# 00003_2020-06-15_05-30-21.net
KiCad netlist of a schematic drawn in EasyEDA
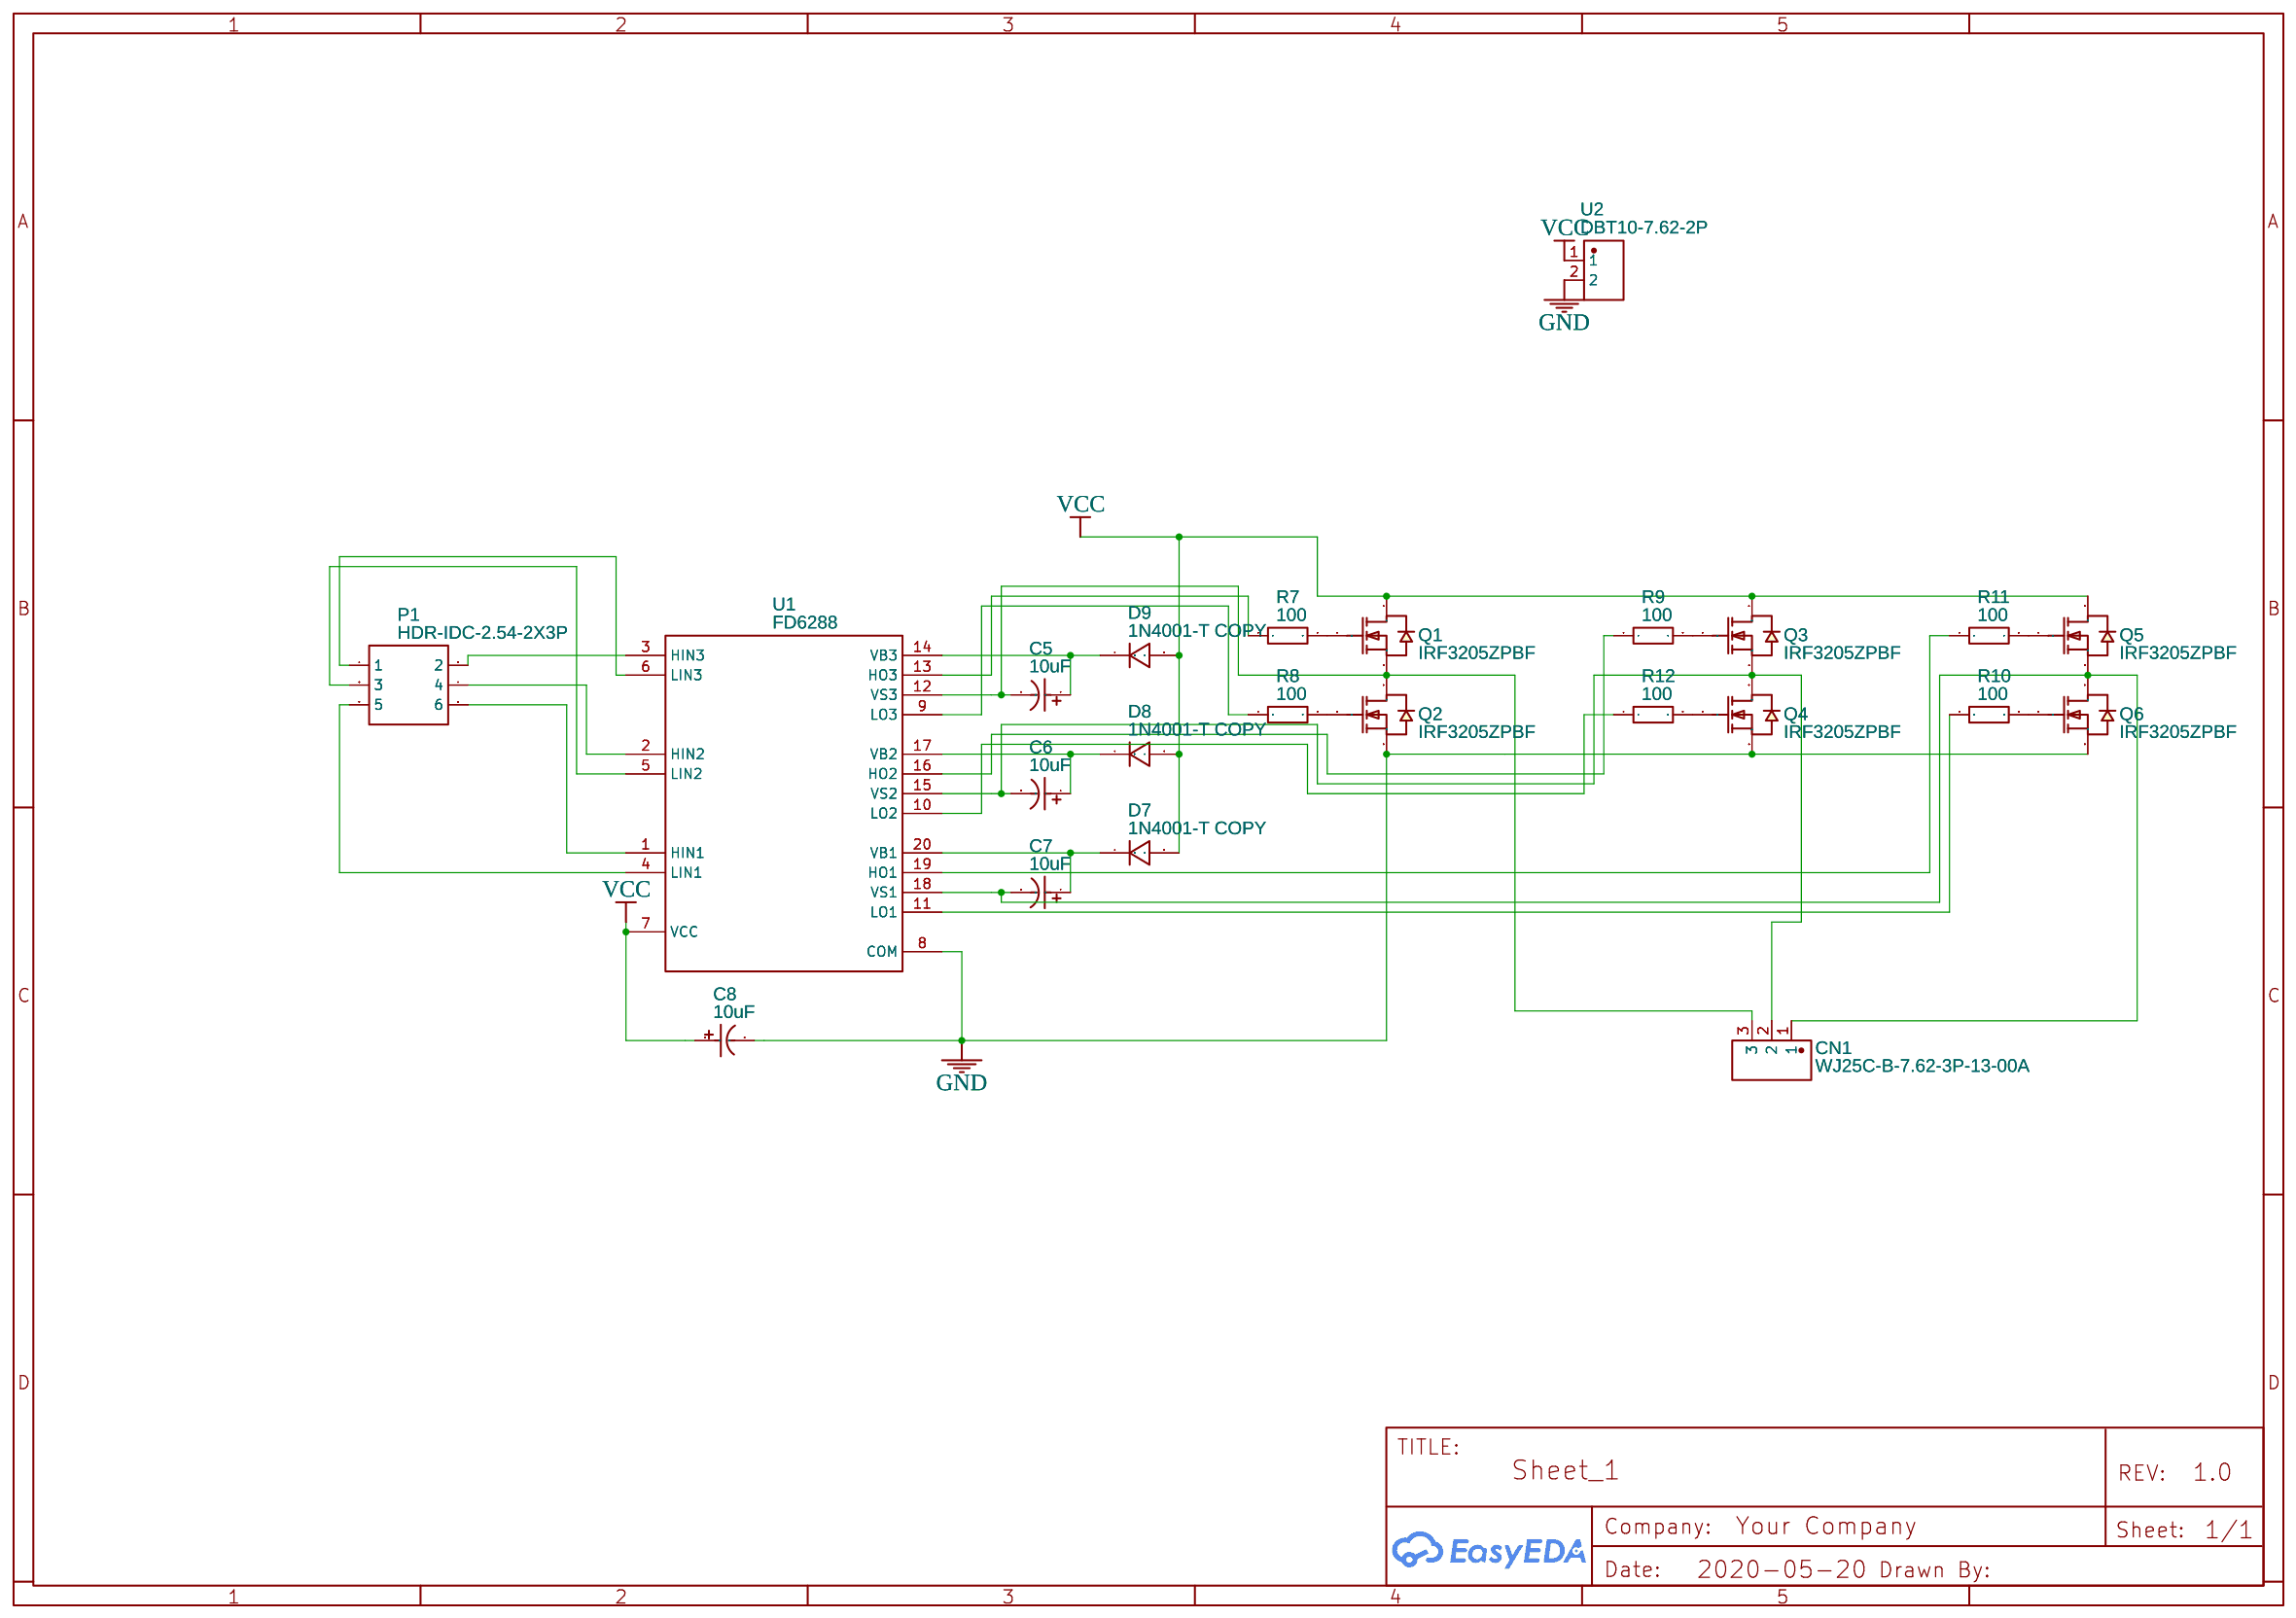
[diagram p0: schematic sheet]

(export (version "E")
  (design (tool "Eeschema 10.0.6"))
  (components
    (comp (ref "C5")
      (value "10uF")
      (fields
        (field (name "BOM_Manufacturer Part") "10uF 25V 5*11")
        (field (name "BOM_Supplier Part") "C43347")
      )
      (libsource (lib "") (part "10uF 25V 5*11"))
    )
    (comp (ref "C6")
      (value "10uF")
      (fields
        (field (name "BOM_Manufacturer Part") "10uF 25V 5*11")
        (field (name "BOM_Supplier Part") "C43347")
      )
      (libsource (lib "") (part "10uF 25V 5*11"))
    )
    (comp (ref "C7")
      (value "10uF")
      (fields
        (field (name "BOM_Manufacturer Part") "10uF 25V 5*11")
        (field (name "BOM_Supplier Part") "C43347")
      )
      (libsource (lib "") (part "10uF 25V 5*11"))
    )
    (comp (ref "C8")
      (value "10uF")
      (fields
        (field (name "BOM_Manufacturer Part") "10uF 25V 5*11")
        (field (name "BOM_Supplier Part") "C43347")
      )
      (libsource (lib "") (part "10uF 25V 5*11_1"))
    )
    (comp (ref "CN1")
      (value "WJ25C-B-7.62-3P-13-00A")
      (fields (field (name "BOM_Supplier Part") "C61583"))
      (libsource (lib "") (part "WJ25C-B-7.62-3P-13-00A"))
    )
    (comp (ref "D7")
      (value "1N4001-T COPY")
      (fields (field (name "BOM_Manufacturer Part") "1N4001-T") (field (name "BOM_Supplier Part") "C99656"))
      (libsource (lib "") (part "1N4001-T COPY"))
    )
    (comp (ref "D8")
      (value "1N4001-T COPY")
      (fields (field (name "BOM_Manufacturer Part") "1N4001-T") (field (name "BOM_Supplier Part") "C99656"))
      (libsource (lib "") (part "1N4001-T COPY"))
    )
    (comp (ref "D9")
      (value "1N4001-T COPY")
      (fields (field (name "BOM_Manufacturer Part") "1N4001-T") (field (name "BOM_Supplier Part") "C99656"))
      (libsource (lib "") (part "1N4001-T COPY"))
    )
    (comp (ref "P1")
      (value "HDR-IDC-2.54-2X3P")
      (fields
        (field (name "BOM_Manufacturer Part") "2X3 2.54mm IDC Box")
        (field (name "BOM_Supplier Part") "C11214")
      )
      (libsource (lib "") (part "HDR-IDC-2.54-2X3P"))
    )
    (comp (ref "Q1")
      (value "IRF3205ZPBF")
      (fields (field (name "BOM_Supplier Part") "C2612"))
      (libsource (lib "") (part "IRF3205ZPBF"))
    )
    (comp (ref "Q2")
      (value "IRF3205ZPBF")
      (fields (field (name "BOM_Supplier Part") "C2612"))
      (libsource (lib "") (part "IRF3205ZPBF"))
    )
    (comp (ref "Q3")
      (value "IRF3205ZPBF")
      (fields (field (name "BOM_Supplier Part") "C2612"))
      (libsource (lib "") (part "IRF3205ZPBF"))
    )
    (comp (ref "Q4")
      (value "IRF3205ZPBF")
      (fields (field (name "BOM_Supplier Part") "C2612"))
      (libsource (lib "") (part "IRF3205ZPBF"))
    )
    (comp (ref "Q5")
      (value "IRF3205ZPBF")
      (fields (field (name "BOM_Supplier Part") "C2612"))
      (libsource (lib "") (part "IRF3205ZPBF"))
    )
    (comp (ref "Q6")
      (value "IRF3205ZPBF")
      (fields (field (name "BOM_Supplier Part") "C2612"))
      (libsource (lib "") (part "IRF3205ZPBF"))
    )
    (comp (ref "R7")
      (value "100")
      (fields (field (name "BOM_Supplier Part") "C120031"))
      (libsource (lib "") (part "CF1/4W-100Ω±5% T52"))
    )
    (comp (ref "R8")
      (value "100")
      (fields (field (name "BOM_Supplier Part") "C120031"))
      (libsource (lib "") (part "CF1/4W-100Ω±5% T52"))
    )
    (comp (ref "R9")
      (value "100")
      (fields (field (name "BOM_Supplier Part") "C120031"))
      (libsource (lib "") (part "CF1/4W-100Ω±5% T52"))
    )
    (comp (ref "R10")
      (value "100")
      (fields (field (name "BOM_Supplier Part") "C120031"))
      (libsource (lib "") (part "CF1/4W-100Ω±5% T52"))
    )
    (comp (ref "R11")
      (value "100")
      (fields (field (name "BOM_Supplier Part") "C120031"))
      (libsource (lib "") (part "CF1/4W-100Ω±5% T52"))
    )
    (comp (ref "R12")
      (value "100")
      (fields (field (name "BOM_Supplier Part") "C120031"))
      (libsource (lib "") (part "CF1/4W-100Ω±5% T52"))
    )
    (comp (ref "U1")
      (value "FD6288")
      (fields (field (name "BOM_Supplier Part") "C97683"))
      (libsource (lib "") (part "FD6288"))
    )
    (comp (ref "U2")
      (value "DBT10-7.62-2P")
      (fields (field (name "BOM_Supplier Part") "C395930"))
      (libsource (lib "") (part "DBT10-7.62-2P"))
    )
  )
  (nets
    (net (code "1") (name "GND") (class "Default")
      (node (ref "C8") (pin "2") (pinfunction "2_2") (pintype "input"))
      (node (ref "Q2") (pin "3") (pinfunction "S_3") (pintype "unspecified"))
      (node (ref "Q4") (pin "3") (pinfunction "S_3") (pintype "unspecified"))
      (node (ref "Q6") (pin "3") (pinfunction "S_3") (pintype "unspecified"))
      (node (ref "U1") (pin "8") (pinfunction "COM_8") (pintype "unspecified"))
      (node (ref "U2") (pin "2") (pinfunction "2_2") (pintype "unspecified"))
    )
    (net (code "2") (name "Net-(D7-C)") (class "Default")
      (node (ref "C7") (pin "1") (pinfunction "1_1") (pintype "input"))
      (node (ref "D7") (pin "1") (pinfunction "C_1") (pintype "unspecified"))
      (node (ref "U1") (pin "20") (pinfunction "VB1_20") (pintype "unspecified"))
    )
    (net (code "3") (name "Net-(D8-C)") (class "Default")
      (node (ref "C6") (pin "1") (pinfunction "1_1") (pintype "input"))
      (node (ref "D8") (pin "1") (pinfunction "C_1") (pintype "unspecified"))
      (node (ref "U1") (pin "17") (pinfunction "VB2_17") (pintype "unspecified"))
    )
    (net (code "4") (name "Net-(D9-C)") (class "Default")
      (node (ref "C5") (pin "1") (pinfunction "1_1") (pintype "input"))
      (node (ref "D9") (pin "1") (pinfunction "C_1") (pintype "unspecified"))
      (node (ref "U1") (pin "14") (pinfunction "VB3_14") (pintype "unspecified"))
    )
    (net (code "5") (name "Net-(Q1-G)") (class "Default")
      (node (ref "Q1") (pin "1") (pinfunction "G_1") (pintype "unspecified"))
      (node (ref "R7") (pin "2") (pinfunction "2_2") (pintype "unspecified"))
    )
    (net (code "6") (name "Net-(Q1-S)") (class "Default")
      (node (ref "C5") (pin "2") (pinfunction "2_2") (pintype "input"))
      (node (ref "CN1") (pin "3") (pinfunction "3_3") (pintype "unspecified"))
      (node (ref "Q1") (pin "3") (pinfunction "S_3") (pintype "unspecified"))
      (node (ref "Q2") (pin "2") (pinfunction "D_2") (pintype "unspecified"))
      (node (ref "U1") (pin "12") (pinfunction "VS3_12") (pintype "unspecified"))
    )
    (net (code "7") (name "Net-(Q2-G)") (class "Default")
      (node (ref "Q2") (pin "1") (pinfunction "G_1") (pintype "unspecified"))
      (node (ref "R8") (pin "2") (pinfunction "2_2") (pintype "unspecified"))
    )
    (net (code "8") (name "Net-(Q3-G)") (class "Default")
      (node (ref "Q3") (pin "1") (pinfunction "G_1") (pintype "unspecified"))
      (node (ref "R9") (pin "2") (pinfunction "2_2") (pintype "unspecified"))
    )
    (net (code "9") (name "Net-(Q3-S)") (class "Default")
      (node (ref "C6") (pin "2") (pinfunction "2_2") (pintype "input"))
      (node (ref "CN1") (pin "2") (pinfunction "2_2") (pintype "unspecified"))
      (node (ref "Q3") (pin "3") (pinfunction "S_3") (pintype "unspecified"))
      (node (ref "Q4") (pin "2") (pinfunction "D_2") (pintype "unspecified"))
      (node (ref "U1") (pin "15") (pinfunction "VS2_15") (pintype "unspecified"))
    )
    (net (code "10") (name "Net-(Q4-G)") (class "Default")
      (node (ref "Q4") (pin "1") (pinfunction "G_1") (pintype "unspecified"))
      (node (ref "R12") (pin "2") (pinfunction "2_2") (pintype "unspecified"))
    )
    (net (code "11") (name "Net-(Q5-G)") (class "Default")
      (node (ref "Q5") (pin "1") (pinfunction "G_1") (pintype "unspecified"))
      (node (ref "R11") (pin "2") (pinfunction "2_2") (pintype "unspecified"))
    )
    (net (code "12") (name "Net-(Q5-S)") (class "Default")
      (node (ref "C7") (pin "2") (pinfunction "2_2") (pintype "input"))
      (node (ref "CN1") (pin "1") (pinfunction "1_1") (pintype "unspecified"))
      (node (ref "Q5") (pin "3") (pinfunction "S_3") (pintype "unspecified"))
      (node (ref "Q6") (pin "2") (pinfunction "D_2") (pintype "unspecified"))
      (node (ref "U1") (pin "18") (pinfunction "VS1_18") (pintype "unspecified"))
    )
    (net (code "13") (name "Net-(Q6-G)") (class "Default")
      (node (ref "Q6") (pin "1") (pinfunction "G_1") (pintype "unspecified"))
      (node (ref "R10") (pin "2") (pinfunction "2_2") (pintype "unspecified"))
    )
    (net (code "14") (name "Net-(U1-HIN1)") (class "Default")
      (node (ref "P1") (pin "6") (pinfunction "6_6") (pintype "unspecified"))
      (node (ref "U1") (pin "1") (pinfunction "HIN1_1") (pintype "unspecified"))
    )
    (net (code "15") (name "Net-(U1-HIN2)") (class "Default")
      (node (ref "P1") (pin "4") (pinfunction "4_4") (pintype "unspecified"))
      (node (ref "U1") (pin "2") (pinfunction "HIN2_2") (pintype "unspecified"))
    )
    (net (code "16") (name "Net-(U1-HIN3)") (class "Default")
      (node (ref "P1") (pin "2") (pinfunction "2_2") (pintype "unspecified"))
      (node (ref "U1") (pin "3") (pinfunction "HIN3_3") (pintype "unspecified"))
    )
    (net (code "17") (name "Net-(U1-HO1)") (class "Default")
      (node (ref "R11") (pin "1") (pinfunction "1_1") (pintype "unspecified"))
      (node (ref "U1") (pin "19") (pinfunction "HO1_19") (pintype "unspecified"))
    )
    (net (code "18") (name "Net-(U1-HO2)") (class "Default")
      (node (ref "R9") (pin "1") (pinfunction "1_1") (pintype "unspecified"))
      (node (ref "U1") (pin "16") (pinfunction "HO2_16") (pintype "unspecified"))
    )
    (net (code "19") (name "Net-(U1-HO3)") (class "Default")
      (node (ref "R7") (pin "1") (pinfunction "1_1") (pintype "unspecified"))
      (node (ref "U1") (pin "13") (pinfunction "HO3_13") (pintype "unspecified"))
    )
    (net (code "20") (name "Net-(U1-LIN1)") (class "Default")
      (node (ref "P1") (pin "5") (pinfunction "5_5") (pintype "unspecified"))
      (node (ref "U1") (pin "4") (pinfunction "LIN1_4") (pintype "unspecified"))
    )
    (net (code "21") (name "Net-(U1-LIN2)") (class "Default")
      (node (ref "P1") (pin "3") (pinfunction "3_3") (pintype "unspecified"))
      (node (ref "U1") (pin "5") (pinfunction "LIN2_5") (pintype "unspecified"))
    )
    (net (code "22") (name "Net-(U1-LIN3)") (class "Default")
      (node (ref "P1") (pin "1") (pinfunction "1_1") (pintype "unspecified"))
      (node (ref "U1") (pin "6") (pinfunction "LIN3_6") (pintype "unspecified"))
    )
    (net (code "23") (name "Net-(U1-LO1)") (class "Default")
      (node (ref "R10") (pin "1") (pinfunction "1_1") (pintype "unspecified"))
      (node (ref "U1") (pin "11") (pinfunction "LO1_11") (pintype "unspecified"))
    )
    (net (code "24") (name "Net-(U1-LO2)") (class "Default")
      (node (ref "R12") (pin "1") (pinfunction "1_1") (pintype "unspecified"))
      (node (ref "U1") (pin "10") (pinfunction "LO2_10") (pintype "unspecified"))
    )
    (net (code "25") (name "Net-(U1-LO3)") (class "Default")
      (node (ref "R8") (pin "1") (pinfunction "1_1") (pintype "unspecified"))
      (node (ref "U1") (pin "9") (pinfunction "LO3_9") (pintype "unspecified"))
    )
    (net (code "26") (name "VCC") (class "Default")
      (node (ref "C8") (pin "1") (pinfunction "1_1") (pintype "input"))
      (node (ref "D7") (pin "2") (pinfunction "A_2") (pintype "unspecified"))
      (node (ref "D8") (pin "2") (pinfunction "A_2") (pintype "unspecified"))
      (node (ref "D9") (pin "2") (pinfunction "A_2") (pintype "unspecified"))
      (node (ref "Q1") (pin "2") (pinfunction "D_2") (pintype "unspecified"))
      (node (ref "Q3") (pin "2") (pinfunction "D_2") (pintype "unspecified"))
      (node (ref "Q5") (pin "2") (pinfunction "D_2") (pintype "unspecified"))
      (node (ref "U1") (pin "7") (pinfunction "VCC_7") (pintype "unspecified"))
      (node (ref "U2") (pin "1") (pinfunction "1_1") (pintype "unspecified"))
    )
  )
)
